# polytag.net
KiCad netlist of a schematic drawn in EAGLE
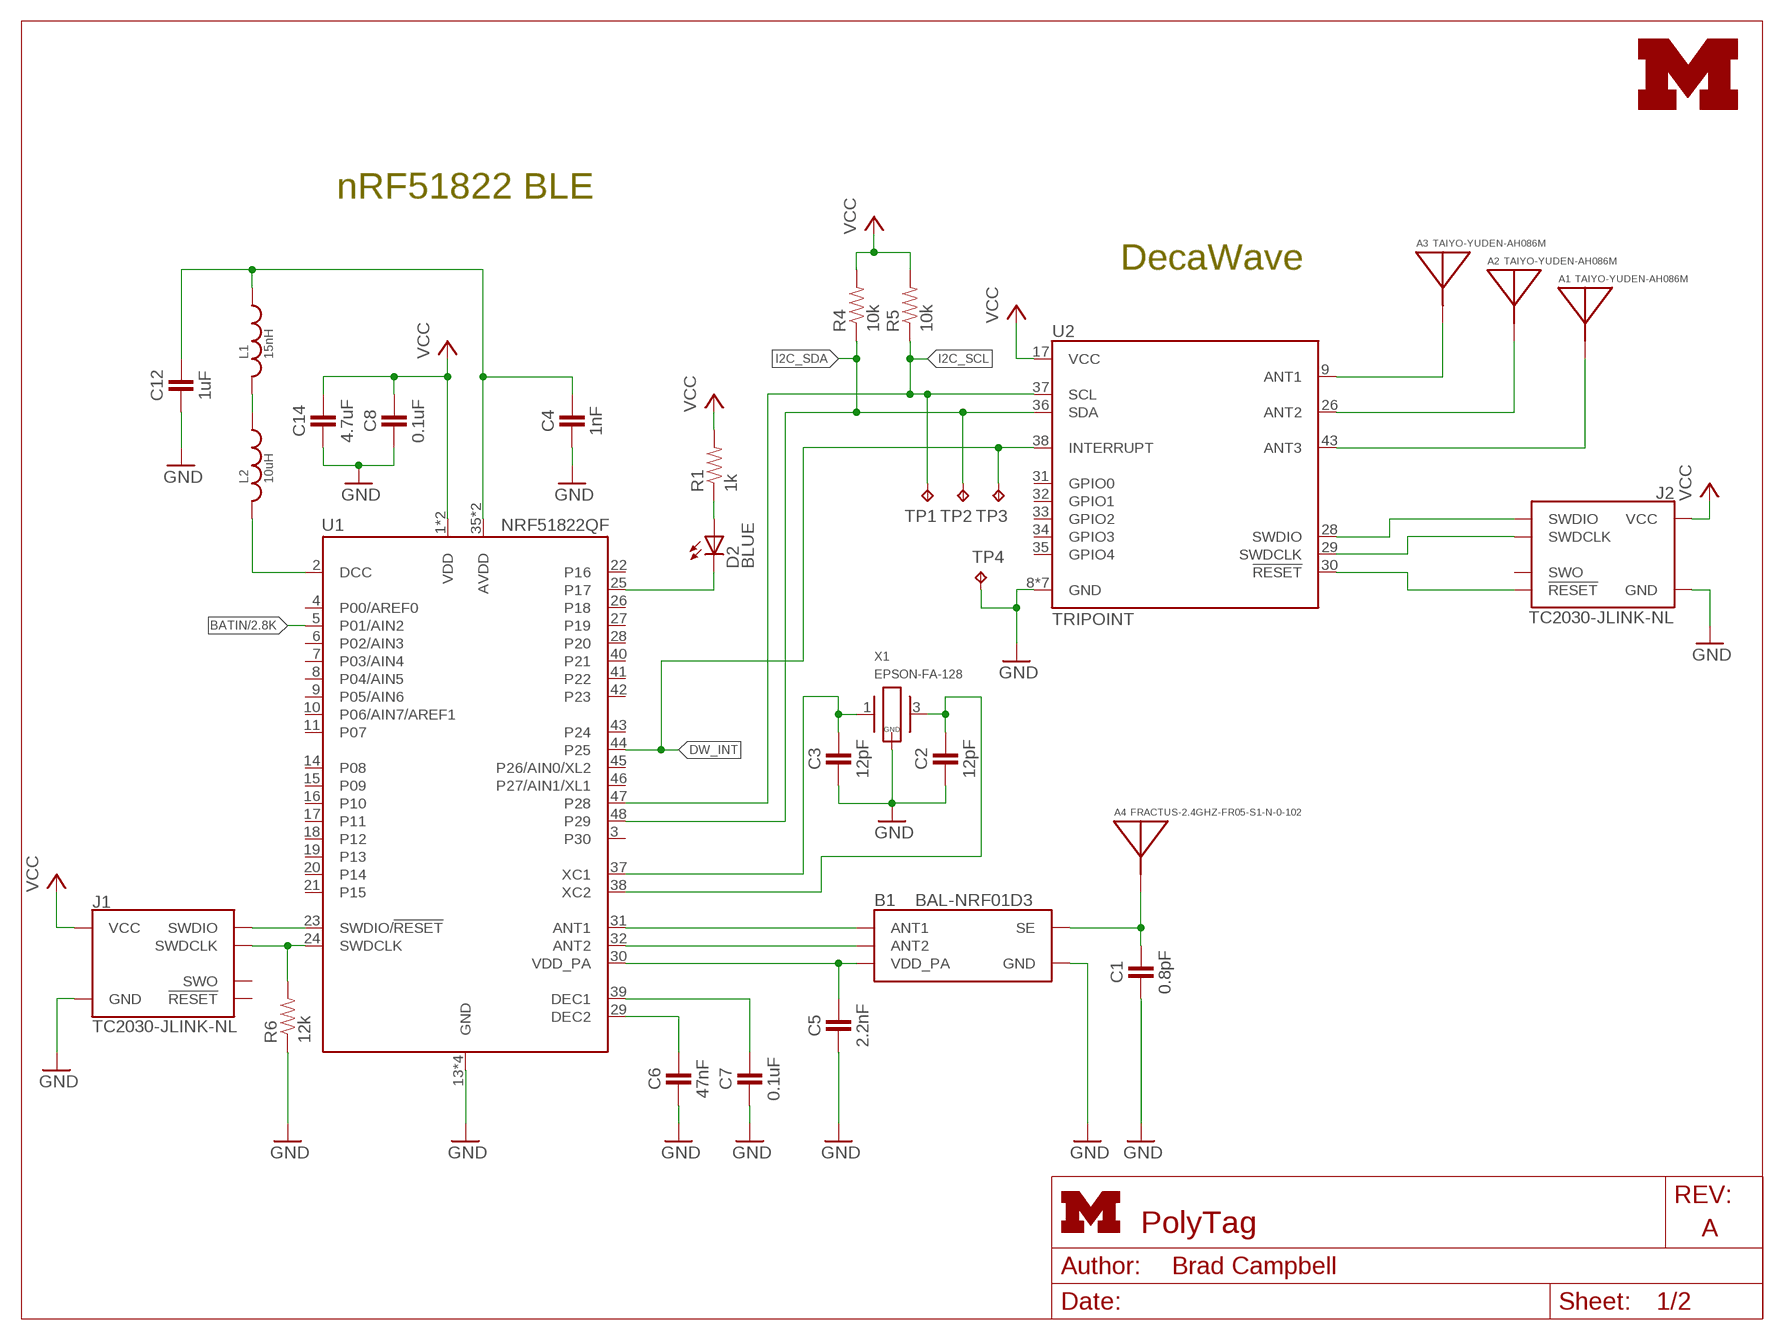
[diagram p0: schematic, sheet 1]
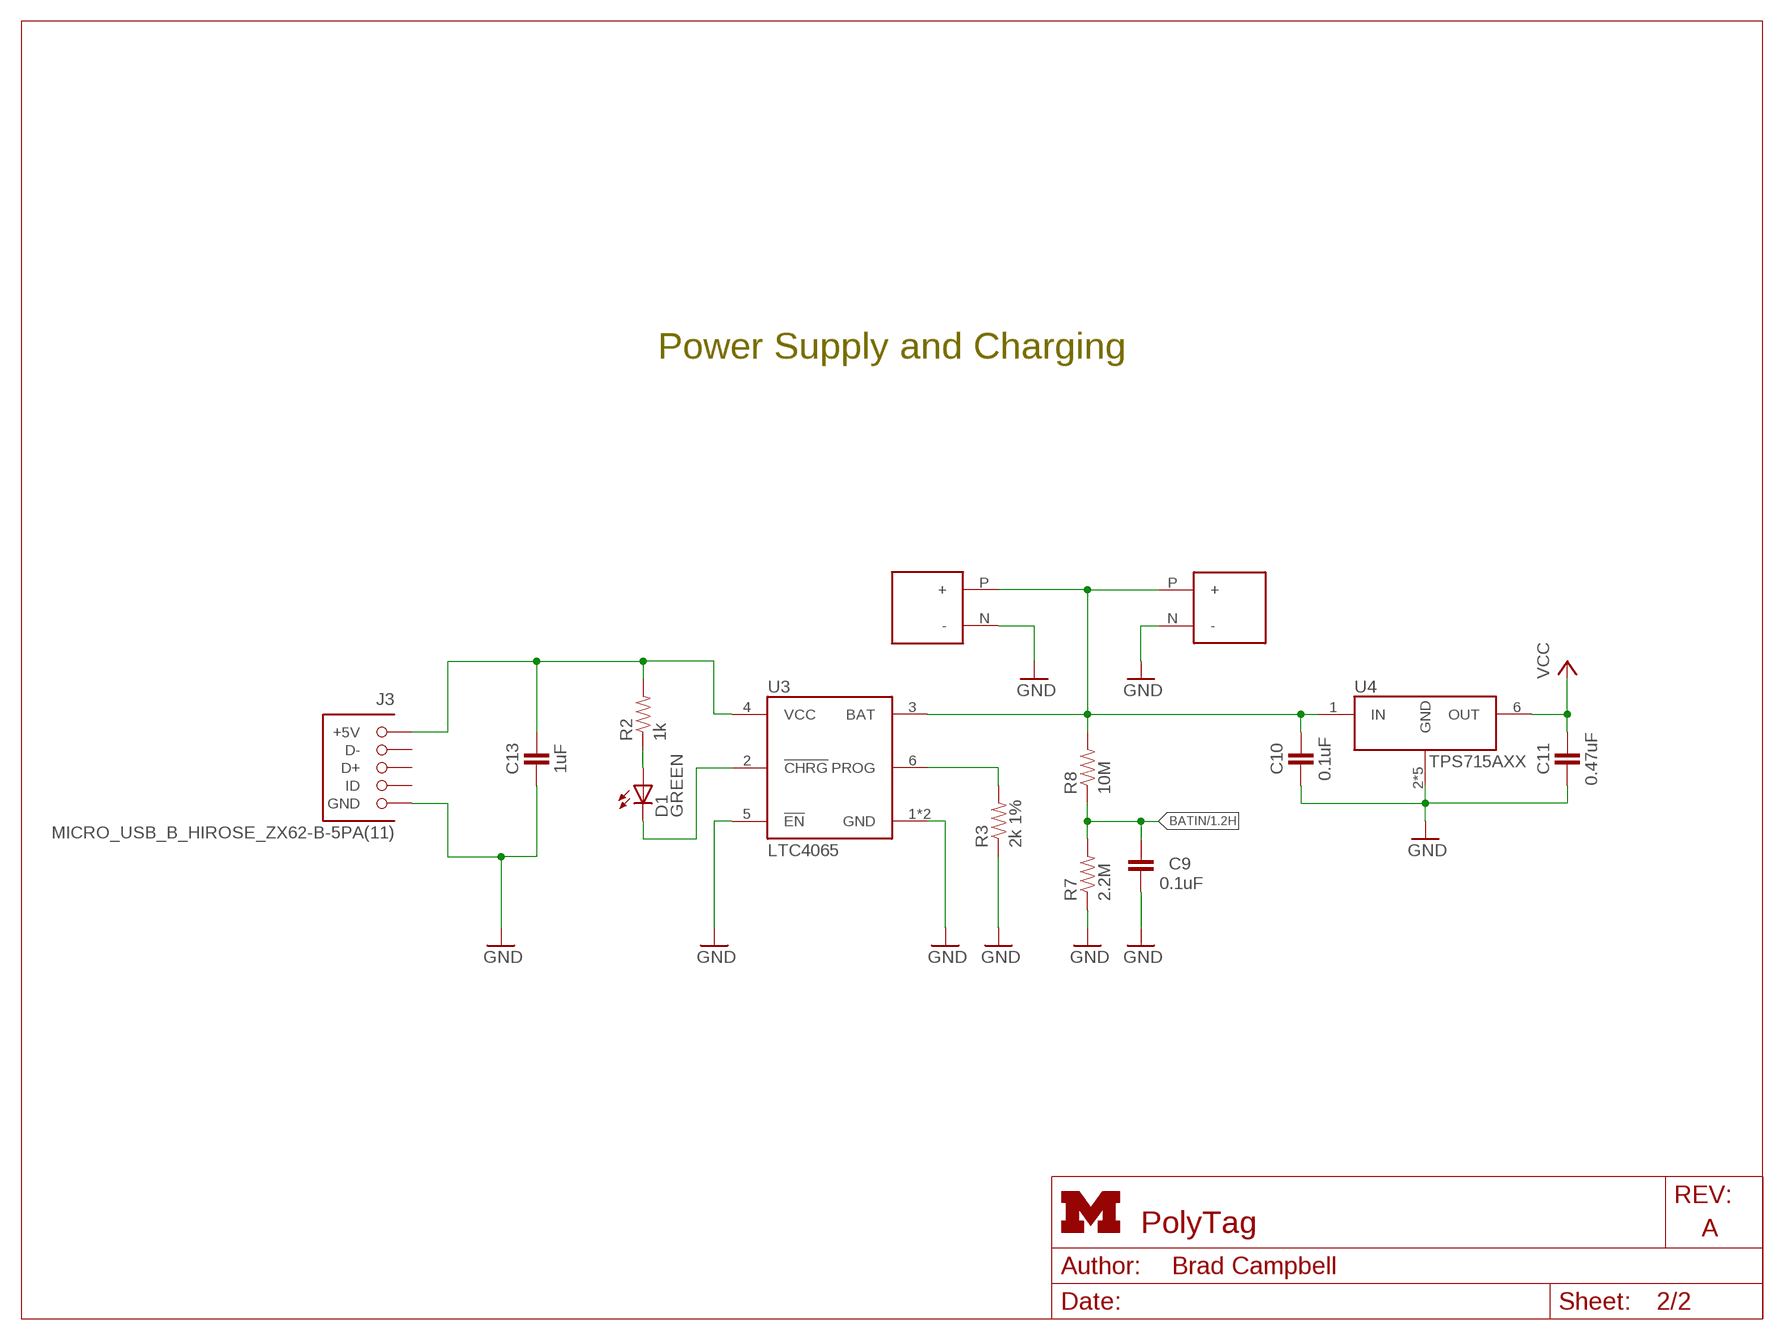
[diagram p1: schematic, sheet 2]

(export (version "E")
  (design (tool "Eeschema 10.0.6"))
  (components
    (comp (ref "A1")
      (value "TAIYO-YUDEN-AH086M")
      (footprint "eagle-import:TAIYO-YUDEN-AH086M")
      (libsource (lib "eagle-import") (part "TAIYO-YUDEN-AH086M"))
    )
    (comp (ref "A2")
      (value "TAIYO-YUDEN-AH086M")
      (footprint "eagle-import:TAIYO-YUDEN-AH086M")
      (libsource (lib "eagle-import") (part "TAIYO-YUDEN-AH086M"))
    )
    (comp (ref "A3")
      (value "TAIYO-YUDEN-AH086M")
      (footprint "eagle-import:TAIYO-YUDEN-AH086M")
      (libsource (lib "eagle-import") (part "TAIYO-YUDEN-AH086M"))
    )
    (comp (ref "A4")
      (value "FRACTUS-2.4GHZ-FR05-S1-N-0-102")
      (footprint "eagle-import:FRACTUS-ANTENNA-FR05-S1-N-0-102")
      (libsource (lib "eagle-import") (part "FRACTUS-2.4GHZ-FR05-S1-N-0-102"))
    )
    (comp (ref "B1")
      (value "BAL-NRF01D3")
      (footprint "eagle-import:BAL-NRF01D3")
      (libsource (lib "eagle-import") (part "BAL-NRF01D3"))
    )
    (comp (ref "C1")
      (value "0.8pF")
      (footprint "eagle-import:0402_CAP")
      (libsource (lib "eagle-import") (part "CAPACITOR"))
    )
    (comp (ref "C2")
      (value "12pF")
      (footprint "eagle-import:0402_CAP")
      (libsource (lib "eagle-import") (part "CAPACITOR"))
    )
    (comp (ref "C3")
      (value "12pF")
      (footprint "eagle-import:0402_CAP")
      (libsource (lib "eagle-import") (part "CAPACITOR"))
    )
    (comp (ref "C4")
      (value "1nF")
      (footprint "eagle-import:0402_CAP")
      (libsource (lib "eagle-import") (part "CAPACITOR"))
    )
    (comp (ref "C5")
      (value "2.2nF")
      (footprint "eagle-import:0402_CAP")
      (libsource (lib "eagle-import") (part "CAPACITOR"))
    )
    (comp (ref "C6")
      (value "47nF")
      (footprint "eagle-import:0402_CAP")
      (libsource (lib "eagle-import") (part "CAPACITOR"))
    )
    (comp (ref "C7")
      (value "0.1uF")
      (footprint "eagle-import:0402_CAP")
      (libsource (lib "eagle-import") (part "CAPACITOR"))
    )
    (comp (ref "C8")
      (value "0.1uF")
      (footprint "eagle-import:0402_CAP")
      (libsource (lib "eagle-import") (part "CAPACITOR"))
    )
    (comp (ref "C12")
      (value "1uF")
      (footprint "eagle-import:0402_CAP")
      (libsource (lib "eagle-import") (part "CAPACITOR"))
    )
    (comp (ref "C14")
      (value "4.7uF")
      (footprint "eagle-import:0402_CAP")
      (libsource (lib "eagle-import") (part "CAPACITOR"))
    )
    (comp (ref "D2")
      (value "BLUE")
      (footprint "eagle-import:LED-0603")
      (libsource (lib "eagle-import") (part "LED0603"))
    )
    (comp (ref "J1")
      (value "TC2030-JLINK-NL")
      (footprint "eagle-import:TC2030-IDC-NL")
      (libsource (lib "eagle-import") (part "TC2030-JLINK-NL"))
    )
    (comp (ref "J2")
      (value "TC2030-JLINK-NL")
      (footprint "eagle-import:TC2030-IDC-NL")
      (libsource (lib "eagle-import") (part "TC2030-JLINK-NL"))
    )
    (comp (ref "L1")
      (value "15nH")
      (footprint "eagle-import:0402_CAP")
      (libsource (lib "eagle-import") (part "INDUCTOR0402"))
    )
    (comp (ref "L2")
      (value "10uH")
      (footprint "eagle-import:0603_CAP")
      (libsource (lib "eagle-import") (part "INDUCTOR0603"))
    )
    (comp (ref "LOGO1")
      (value "UMICH_SOLID_SMALL")
      (footprint "eagle-import:UMICH_SOLID_75MIL")
      (libsource (lib "eagle-import") (part "UMICH_SOLID_SMALL"))
    )
    (comp (ref "R1")
      (value "1k")
      (footprint "eagle-import:0402_RES")
      (libsource (lib "eagle-import") (part "RESISTOR0402_RES"))
    )
    (comp (ref "R4")
      (value "10k")
      (footprint "eagle-import:0402_RES")
      (libsource (lib "eagle-import") (part "RESISTOR0402_RES"))
    )
    (comp (ref "R5")
      (value "10k")
      (footprint "eagle-import:0402_RES")
      (libsource (lib "eagle-import") (part "RESISTOR0402_RES"))
    )
    (comp (ref "R6")
      (value "12k")
      (footprint "eagle-import:0402_RES")
      (libsource (lib "eagle-import") (part "RESISTOR0402_RES"))
    )
    (comp (ref "TP1")
      (value "TPTP06SQ")
      (footprint "eagle-import:TP06SQ")
      (libsource (lib "eagle-import") (part "TPTP06SQ"))
    )
    (comp (ref "TP2")
      (value "TPTP06SQ")
      (footprint "eagle-import:TP06SQ")
      (libsource (lib "eagle-import") (part "TPTP06SQ"))
    )
    (comp (ref "TP3")
      (value "TPTP06SQ")
      (footprint "eagle-import:TP06SQ")
      (libsource (lib "eagle-import") (part "TPTP06SQ"))
    )
    (comp (ref "TP4")
      (value "TPTP06SQ")
      (footprint "eagle-import:TP06SQ")
      (libsource (lib "eagle-import") (part "TPTP06SQ"))
    )
    (comp (ref "U1")
      (value "NRF51822QF")
      (footprint "eagle-import:QFN-48-6MM")
      (libsource (lib "eagle-import") (part "NRF51822QF"))
    )
    (comp (ref "U2")
      (value "TRIPOINT")
      (footprint "eagle-import:TRIPOINT")
      (libsource (lib "eagle-import") (part "TRIPOINT"))
    )
    (comp (ref "X1")
      (value "EPSON-FA-128")
      (footprint "eagle-import:FA-128")
      (libsource (lib "eagle-import") (part "EPSON-FA-128"))
    )
    (comp (ref "C9")
      (value "0.1uF")
      (footprint "eagle-import:0402_CAP")
      (libsource (lib "eagle-import") (part "CAPACITOR"))
    )
    (comp (ref "C10")
      (value "0.1uF")
      (footprint "eagle-import:0402_CAP")
      (libsource (lib "eagle-import") (part "CAPACITOR"))
    )
    (comp (ref "C11")
      (value "0.47uF")
      (footprint "eagle-import:0402_CAP")
      (libsource (lib "eagle-import") (part "CAPACITOR"))
    )
    (comp (ref "C13")
      (value "1uF")
      (footprint "eagle-import:0402_CAP")
      (libsource (lib "eagle-import") (part "CAPACITOR"))
    )
    (comp (ref "D1")
      (value "GREEN")
      (footprint "eagle-import:LED-0603")
      (libsource (lib "eagle-import") (part "LED0603"))
    )
    (comp (ref "J3")
      (value "MICRO_USB_B_HIROSE_ZX62-B-5PA(11)")
      (footprint "eagle-import:USB_MICRO_B-HIROSE-ZX62-B-5PA(11)")
      (libsource (lib "eagle-import") (part "MICRO_USB_B_HIROSE_ZX62-B-5PA(11)"))
    )
    (comp (ref "J4")
      (value "BAT_HOLE")
      (footprint "eagle-import:BATTERY_HOLE")
      (libsource (lib "eagle-import") (part "BAT_HOLE"))
    )
    (comp (ref "J5")
      (value "BAT_HOLE")
      (footprint "eagle-import:BATTERY_HOLE")
      (libsource (lib "eagle-import") (part "BAT_HOLE"))
    )
    (comp (ref "R2")
      (value "1k")
      (footprint "eagle-import:0402_RES")
      (libsource (lib "eagle-import") (part "RESISTOR0402_RES"))
    )
    (comp (ref "R3")
      (value "2k 1%")
      (footprint "eagle-import:0402_RES")
      (libsource (lib "eagle-import") (part "RESISTOR0402_RES"))
    )
    (comp (ref "R7")
      (value "2.2M")
      (footprint "eagle-import:0402_RES")
      (libsource (lib "eagle-import") (part "RESISTOR0402_RES"))
    )
    (comp (ref "R8")
      (value "10M")
      (footprint "eagle-import:0402_RES")
      (libsource (lib "eagle-import") (part "RESISTOR0402_RES"))
    )
    (comp (ref "U3")
      (value "LTC4065")
      (footprint "eagle-import:DFN-6_2MM")
      (libsource (lib "eagle-import") (part "LTC4065"))
    )
    (comp (ref "U4")
      (value "TPS715AXX")
      (footprint "eagle-import:WDFN-6")
      (libsource (lib "eagle-import") (part "TPS715AXX"))
    )
  )
  (nets
    (net (code "1") (name "BATIN") (class "Default")
      (node (ref "C9") (pin "2") (pinfunction "2_2") (pintype "bidirectional"))
      (node (ref "R7") (pin "2") (pinfunction "2_2") (pintype "passive"))
      (node (ref "R8") (pin "1") (pinfunction "1_1") (pintype "passive"))
      (node (ref "U1") (pin "5") (pinfunction "P01/AIN2_5") (pintype "bidirectional"))
    )
    (net (code "2") (name "DW_INT") (class "Default")
      (node (ref "TP3") (pin "TP") (pinfunction "TP_TP") (pintype "input"))
      (node (ref "U1") (pin "44") (pinfunction "P25_44") (pintype "bidirectional"))
      (node (ref "U2") (pin "38") (pinfunction "INTERRUPT_38") (pintype "bidirectional"))
    )
    (net (code "3") (name "GND") (class "Default")
      (node (ref "B1") (pin "GND") (pinfunction "GND_GND") (pintype "bidirectional"))
      (node (ref "C1") (pin "2") (pinfunction "2_2") (pintype "bidirectional"))
      (node (ref "C10") (pin "2") (pinfunction "2_2") (pintype "bidirectional"))
      (node (ref "C11") (pin "2") (pinfunction "2_2") (pintype "bidirectional"))
      (node (ref "C12") (pin "2") (pinfunction "2_2") (pintype "bidirectional"))
      (node (ref "C13") (pin "2") (pinfunction "2_2") (pintype "bidirectional"))
      (node (ref "C14") (pin "2") (pinfunction "2_2") (pintype "bidirectional"))
      (node (ref "C2") (pin "2") (pinfunction "2_2") (pintype "bidirectional"))
      (node (ref "C3") (pin "2") (pinfunction "2_2") (pintype "bidirectional"))
      (node (ref "C4") (pin "2") (pinfunction "2_2") (pintype "bidirectional"))
      (node (ref "C5") (pin "2") (pinfunction "2_2") (pintype "bidirectional"))
      (node (ref "C6") (pin "2") (pinfunction "2_2") (pintype "bidirectional"))
      (node (ref "C7") (pin "2") (pinfunction "2_2") (pintype "bidirectional"))
      (node (ref "C8") (pin "2") (pinfunction "2_2") (pintype "bidirectional"))
      (node (ref "C9") (pin "1") (pinfunction "1_1") (pintype "bidirectional"))
      (node (ref "J1") (pin "5") (pinfunction "GND_5") (pintype "bidirectional"))
      (node (ref "J2") (pin "5") (pinfunction "GND_5") (pintype "bidirectional"))
      (node (ref "J3") (pin "5") (pinfunction "GND_5") (pintype "bidirectional"))
      (node (ref "J4") (pin "N") (pinfunction "-_N") (pintype "bidirectional"))
      (node (ref "J5") (pin "N") (pinfunction "-_N") (pintype "bidirectional"))
      (node (ref "R3") (pin "1") (pinfunction "1_1") (pintype "passive"))
      (node (ref "R6") (pin "1") (pinfunction "1_1") (pintype "passive"))
      (node (ref "R7") (pin "1") (pinfunction "1_1") (pintype "passive"))
      (node (ref "TP4") (pin "TP") (pinfunction "TP_TP") (pintype "input"))
      (node (ref "U1") (pin "13") (pinfunction "GND_13") (pintype "bidirectional"))
      (node (ref "U1") (pin "33") (pinfunction "GND_33") (pintype "bidirectional"))
      (node (ref "U1") (pin "34") (pinfunction "GND_34") (pintype "bidirectional"))
      (node (ref "U1") (pin "GND") (pinfunction "GND_GND") (pintype "bidirectional"))
      (node (ref "U2") (pin "10") (pinfunction "GND_10") (pintype "bidirectional"))
      (node (ref "U2") (pin "18") (pinfunction "GND_18") (pintype "bidirectional"))
      (node (ref "U2") (pin "25") (pinfunction "GND_25") (pintype "bidirectional"))
      (node (ref "U2") (pin "27") (pinfunction "GND_27") (pintype "bidirectional"))
      (node (ref "U2") (pin "42") (pinfunction "GND_42") (pintype "bidirectional"))
      (node (ref "U2") (pin "44") (pinfunction "GND_44") (pintype "bidirectional"))
      (node (ref "U2") (pin "8") (pinfunction "GND_8") (pintype "bidirectional"))
      (node (ref "U3") (pin "1") (pinfunction "GND_1") (pintype "bidirectional"))
      (node (ref "U3") (pin "5") (pinfunction "~{EN}_5") (pintype "bidirectional"))
      (node (ref "U3") (pin "7") (pinfunction "GND_7") (pintype "bidirectional"))
      (node (ref "U4") (pin "2") (pinfunction "GND_2") (pintype "bidirectional"))
      (node (ref "U4") (pin "3") (pinfunction "GND_3") (pintype "bidirectional"))
      (node (ref "U4") (pin "4") (pinfunction "GND_4") (pintype "bidirectional"))
      (node (ref "U4") (pin "5") (pinfunction "GND_5") (pintype "bidirectional"))
      (node (ref "U4") (pin "TP3") (pinfunction "GND_TP3") (pintype "bidirectional"))
      (node (ref "X1") (pin "2") (pinfunction "GND_2") (pintype "bidirectional"))
      (node (ref "X1") (pin "4") (pinfunction "GND_4") (pintype "bidirectional"))
    )
    (net (code "4") (name "I2C_SCL") (class "Default")
      (node (ref "R5") (pin "1") (pinfunction "1_1") (pintype "passive"))
      (node (ref "TP1") (pin "TP") (pinfunction "TP_TP") (pintype "input"))
      (node (ref "U1") (pin "47") (pinfunction "P28_47") (pintype "bidirectional"))
      (node (ref "U2") (pin "37") (pinfunction "SCL_37") (pintype "bidirectional"))
    )
    (net (code "5") (name "I2C_SDA") (class "Default")
      (node (ref "R4") (pin "1") (pinfunction "1_1") (pintype "passive"))
      (node (ref "TP2") (pin "TP") (pinfunction "TP_TP") (pintype "input"))
      (node (ref "U1") (pin "48") (pinfunction "P29_48") (pintype "bidirectional"))
      (node (ref "U2") (pin "36") (pinfunction "SDA_36") (pintype "bidirectional"))
    )
    (net (code "6") (name "Net-(A1-ANTENNA)") (class "Default")
      (node (ref "A1") (pin "A") (pinfunction "ANTENNA_A") (pintype "bidirectional"))
      (node (ref "U2") (pin "43") (pinfunction "ANT3_43") (pintype "bidirectional"))
    )
    (net (code "7") (name "Net-(A2-ANTENNA)") (class "Default")
      (node (ref "A2") (pin "A") (pinfunction "ANTENNA_A") (pintype "bidirectional"))
      (node (ref "U2") (pin "26") (pinfunction "ANT2_26") (pintype "bidirectional"))
    )
    (net (code "8") (name "Net-(A3-ANTENNA)") (class "Default")
      (node (ref "A3") (pin "A") (pinfunction "ANTENNA_A") (pintype "bidirectional"))
      (node (ref "U2") (pin "9") (pinfunction "ANT1_9") (pintype "bidirectional"))
    )
    (net (code "9") (name "Net-(A4-ANTENNA)") (class "Default")
      (node (ref "A4") (pin "1") (pinfunction "ANTENNA_1") (pintype "bidirectional"))
      (node (ref "B1") (pin "SE") (pinfunction "SE_SE") (pintype "bidirectional"))
      (node (ref "C1") (pin "1") (pinfunction "1_1") (pintype "bidirectional"))
    )
    (net (code "10") (name "Net-(B1-VDD_PA)") (class "Default")
      (node (ref "B1") (pin "VCC") (pinfunction "VDD_PA_VCC") (pintype "bidirectional"))
      (node (ref "C5") (pin "1") (pinfunction "1_1") (pintype "bidirectional"))
      (node (ref "U1") (pin "30") (pinfunction "VDD_PA_30") (pintype "bidirectional"))
    )
    (net (code "11") (name "Net-(C12-Pad1)") (class "Default")
      (node (ref "C12") (pin "1") (pinfunction "1_1") (pintype "bidirectional"))
      (node (ref "C4") (pin "1") (pinfunction "1_1") (pintype "bidirectional"))
      (node (ref "L1") (pin "1") (pinfunction "1_1") (pintype "bidirectional"))
      (node (ref "U1") (pin "35") (pinfunction "AVDD_35") (pintype "bidirectional"))
      (node (ref "U1") (pin "36") (pinfunction "AVDD_36") (pintype "bidirectional"))
    )
    (net (code "12") (name "Net-(D1-PadA)") (class "Default")
      (node (ref "D1") (pin "A") (pinfunction "A_A") (pintype "passive"))
      (node (ref "R2") (pin "1") (pinfunction "1_1") (pintype "passive"))
    )
    (net (code "13") (name "Net-(D2-PadA)") (class "Default")
      (node (ref "D2") (pin "A") (pinfunction "A_A") (pintype "passive"))
      (node (ref "R1") (pin "1") (pinfunction "1_1") (pintype "passive"))
    )
    (net (code "14") (name "Net-(J1-SWDCLK)") (class "Default")
      (node (ref "J1") (pin "4") (pinfunction "SWDCLK_4") (pintype "bidirectional"))
      (node (ref "R6") (pin "2") (pinfunction "2_2") (pintype "passive"))
      (node (ref "U1") (pin "24") (pinfunction "SWDCLK_24") (pintype "bidirectional"))
    )
    (net (code "15") (name "Net-(J1-SWDIO)") (class "Default")
      (node (ref "J1") (pin "2") (pinfunction "SWDIO_2") (pintype "bidirectional"))
      (node (ref "U1") (pin "23") (pinfunction "SWDIO/~{RESET}_23") (pintype "bidirectional"))
    )
    (net (code "16") (name "Net-(J2-SWDCLK)") (class "Default")
      (node (ref "J2") (pin "4") (pinfunction "SWDCLK_4") (pintype "bidirectional"))
      (node (ref "U2") (pin "29") (pinfunction "SWDCLK_29") (pintype "bidirectional"))
    )
    (net (code "17") (name "Net-(J2-SWDIO)") (class "Default")
      (node (ref "J2") (pin "2") (pinfunction "SWDIO_2") (pintype "bidirectional"))
      (node (ref "U2") (pin "28") (pinfunction "SWDIO_28") (pintype "bidirectional"))
    )
    (net (code "18") (name "Net-(J2-~{RESET})") (class "Default")
      (node (ref "J2") (pin "3") (pinfunction "~{RESET}_3") (pintype "bidirectional"))
      (node (ref "U2") (pin "30") (pinfunction "~{RESET}_30") (pintype "bidirectional"))
    )
    (net (code "19") (name "Net-(J3-+5V)") (class "Default")
      (node (ref "C13") (pin "1") (pinfunction "1_1") (pintype "bidirectional"))
      (node (ref "J3") (pin "1") (pinfunction "+5V_1") (pintype "bidirectional"))
      (node (ref "R2") (pin "2") (pinfunction "2_2") (pintype "passive"))
      (node (ref "U3") (pin "4") (pinfunction "VCC_4") (pintype "bidirectional"))
    )
    (net (code "20") (name "Net-(J4-+)") (class "Default")
      (node (ref "C10") (pin "1") (pinfunction "1_1") (pintype "bidirectional"))
      (node (ref "J4") (pin "P") (pinfunction "+_P") (pintype "bidirectional"))
      (node (ref "J5") (pin "P") (pinfunction "+_P") (pintype "bidirectional"))
      (node (ref "R8") (pin "2") (pinfunction "2_2") (pintype "passive"))
      (node (ref "U3") (pin "3") (pinfunction "BAT_3") (pintype "bidirectional"))
      (node (ref "U4") (pin "1") (pinfunction "IN_1") (pintype "bidirectional"))
    )
    (net (code "21") (name "Net-(L1-Pad2)") (class "Default")
      (node (ref "L1") (pin "2") (pinfunction "2_2") (pintype "bidirectional"))
      (node (ref "L2") (pin "1") (pinfunction "1_1") (pintype "bidirectional"))
    )
    (net (code "22") (name "Net-(U1-ANT1)") (class "Default")
      (node (ref "B1") (pin "ANT1") (pinfunction "ANT1_ANT1") (pintype "bidirectional"))
      (node (ref "U1") (pin "31") (pinfunction "ANT1_31") (pintype "bidirectional"))
    )
    (net (code "23") (name "Net-(U1-ANT2)") (class "Default")
      (node (ref "B1") (pin "ANT2") (pinfunction "ANT2_ANT2") (pintype "bidirectional"))
      (node (ref "U1") (pin "32") (pinfunction "ANT2_32") (pintype "bidirectional"))
    )
    (net (code "24") (name "Net-(U1-DCC)") (class "Default")
      (node (ref "L2") (pin "2") (pinfunction "2_2") (pintype "bidirectional"))
      (node (ref "U1") (pin "2") (pinfunction "DCC_2") (pintype "bidirectional"))
    )
    (net (code "25") (name "Net-(U1-DEC1)") (class "Default")
      (node (ref "C7") (pin "1") (pinfunction "1_1") (pintype "bidirectional"))
      (node (ref "U1") (pin "39") (pinfunction "DEC1_39") (pintype "bidirectional"))
    )
    (net (code "26") (name "Net-(U1-DEC2)") (class "Default")
      (node (ref "C6") (pin "1") (pinfunction "1_1") (pintype "bidirectional"))
      (node (ref "U1") (pin "29") (pinfunction "DEC2_29") (pintype "bidirectional"))
    )
    (net (code "27") (name "Net-(U1-P17)") (class "Default")
      (node (ref "D2") (pin "C") (pinfunction "C_C") (pintype "passive"))
      (node (ref "U1") (pin "25") (pinfunction "P17_25") (pintype "bidirectional"))
    )
    (net (code "28") (name "Net-(U1-XC1)") (class "Default")
      (node (ref "C3") (pin "1") (pinfunction "1_1") (pintype "bidirectional"))
      (node (ref "U1") (pin "37") (pinfunction "XC1_37") (pintype "bidirectional"))
      (node (ref "X1") (pin "1") (pinfunction "1_1") (pintype "bidirectional"))
    )
    (net (code "29") (name "Net-(U1-XC2)") (class "Default")
      (node (ref "C2") (pin "1") (pinfunction "1_1") (pintype "bidirectional"))
      (node (ref "U1") (pin "38") (pinfunction "XC2_38") (pintype "bidirectional"))
      (node (ref "X1") (pin "3") (pinfunction "2_3") (pintype "bidirectional"))
    )
    (net (code "30") (name "Net-(U3-PROG)") (class "Default")
      (node (ref "R3") (pin "2") (pinfunction "2_2") (pintype "passive"))
      (node (ref "U3") (pin "6") (pinfunction "PROG_6") (pintype "bidirectional"))
    )
    (net (code "31") (name "Net-(U3-~{CHRG})") (class "Default")
      (node (ref "D1") (pin "C") (pinfunction "C_C") (pintype "passive"))
      (node (ref "U3") (pin "2") (pinfunction "~{CHRG}_2") (pintype "bidirectional"))
    )
    (net (code "32") (name "VCC") (class "Default")
      (node (ref "C11") (pin "1") (pinfunction "1_1") (pintype "bidirectional"))
      (node (ref "C14") (pin "1") (pinfunction "1_1") (pintype "bidirectional"))
      (node (ref "C8") (pin "1") (pinfunction "1_1") (pintype "bidirectional"))
      (node (ref "J1") (pin "1") (pinfunction "VCC_1") (pintype "bidirectional"))
      (node (ref "J2") (pin "1") (pinfunction "VCC_1") (pintype "bidirectional"))
      (node (ref "R1") (pin "2") (pinfunction "2_2") (pintype "passive"))
      (node (ref "R4") (pin "2") (pinfunction "2_2") (pintype "passive"))
      (node (ref "R5") (pin "2") (pinfunction "2_2") (pintype "passive"))
      (node (ref "U1") (pin "1") (pinfunction "VDD_1") (pintype "bidirectional"))
      (node (ref "U1") (pin "12") (pinfunction "VDD_12") (pintype "bidirectional"))
      (node (ref "U2") (pin "17") (pinfunction "VCC_17") (pintype "bidirectional"))
      (node (ref "U4") (pin "6") (pinfunction "OUT_6") (pintype "bidirectional"))
    )
    (net (code "33") (name "unconnected-(J1-SWO-Pad6)") (class "Default")
      (node (ref "J1") (pin "6") (pinfunction "SWO_6") (pintype "bidirectional"))
    )
    (net (code "34") (name "unconnected-(J1-~{RESET}-Pad3)") (class "Default")
      (node (ref "J1") (pin "3") (pinfunction "~{RESET}_3") (pintype "bidirectional"))
    )
    (net (code "35") (name "unconnected-(J2-SWO-Pad6)") (class "Default")
      (node (ref "J2") (pin "6") (pinfunction "SWO_6") (pintype "bidirectional"))
    )
    (net (code "36") (name "unconnected-(J3-D+-Pad3)") (class "Default")
      (node (ref "J3") (pin "3") (pinfunction "D+_3") (pintype "bidirectional"))
    )
    (net (code "37") (name "unconnected-(J3-D--Pad2)") (class "Default")
      (node (ref "J3") (pin "2") (pinfunction "D-_2") (pintype "bidirectional"))
    )
    (net (code "38") (name "unconnected-(J3-ID-Pad4)") (class "Default")
      (node (ref "J3") (pin "4") (pinfunction "ID_4") (pintype "bidirectional"))
    )
    (net (code "39") (name "unconnected-(U1-P00{slash}AREF0-Pad4)") (class "Default")
      (node (ref "U1") (pin "4") (pinfunction "P00/AREF0_4") (pintype "bidirectional"))
    )
    (net (code "40") (name "unconnected-(U1-P02{slash}AIN3-Pad6)") (class "Default")
      (node (ref "U1") (pin "6") (pinfunction "P02/AIN3_6") (pintype "bidirectional"))
    )
    (net (code "41") (name "unconnected-(U1-P03{slash}AIN4-Pad7)") (class "Default")
      (node (ref "U1") (pin "7") (pinfunction "P03/AIN4_7") (pintype "bidirectional"))
    )
    (net (code "42") (name "unconnected-(U1-P04{slash}AIN5-Pad8)") (class "Default")
      (node (ref "U1") (pin "8") (pinfunction "P04/AIN5_8") (pintype "bidirectional"))
    )
    (net (code "43") (name "unconnected-(U1-P05{slash}AIN6-Pad9)") (class "Default")
      (node (ref "U1") (pin "9") (pinfunction "P05/AIN6_9") (pintype "bidirectional"))
    )
    (net (code "44") (name "unconnected-(U1-P06{slash}AIN7{slash}AREF1-Pad10)") (class "Default")
      (node (ref "U1") (pin "10") (pinfunction "P06/AIN7/AREF1_10") (pintype "bidirectional"))
    )
    (net (code "45") (name "unconnected-(U1-P07-Pad11)") (class "Default")
      (node (ref "U1") (pin "11") (pinfunction "P07_11") (pintype "bidirectional"))
    )
    (net (code "46") (name "unconnected-(U1-P08-Pad14)") (class "Default")
      (node (ref "U1") (pin "14") (pinfunction "P08_14") (pintype "bidirectional"))
    )
    (net (code "47") (name "unconnected-(U1-P09-Pad15)") (class "Default")
      (node (ref "U1") (pin "15") (pinfunction "P09_15") (pintype "bidirectional"))
    )
    (net (code "48") (name "unconnected-(U1-P10-Pad16)") (class "Default")
      (node (ref "U1") (pin "16") (pinfunction "P10_16") (pintype "bidirectional"))
    )
    (net (code "49") (name "unconnected-(U1-P11-Pad17)") (class "Default")
      (node (ref "U1") (pin "17") (pinfunction "P11_17") (pintype "bidirectional"))
    )
    (net (code "50") (name "unconnected-(U1-P12-Pad18)") (class "Default")
      (node (ref "U1") (pin "18") (pinfunction "P12_18") (pintype "bidirectional"))
    )
    (net (code "51") (name "unconnected-(U1-P13-Pad19)") (class "Default")
      (node (ref "U1") (pin "19") (pinfunction "P13_19") (pintype "bidirectional"))
    )
    (net (code "52") (name "unconnected-(U1-P14-Pad20)") (class "Default")
      (node (ref "U1") (pin "20") (pinfunction "P14_20") (pintype "bidirectional"))
    )
    (net (code "53") (name "unconnected-(U1-P15-Pad21)") (class "Default")
      (node (ref "U1") (pin "21") (pinfunction "P15_21") (pintype "bidirectional"))
    )
    (net (code "54") (name "unconnected-(U1-P16-Pad22)") (class "Default")
      (node (ref "U1") (pin "22") (pinfunction "P16_22") (pintype "bidirectional"))
    )
    (net (code "55") (name "unconnected-(U1-P18-Pad26)") (class "Default")
      (node (ref "U1") (pin "26") (pinfunction "P18_26") (pintype "bidirectional"))
    )
    (net (code "56") (name "unconnected-(U1-P19-Pad27)") (class "Default")
      (node (ref "U1") (pin "27") (pinfunction "P19_27") (pintype "bidirectional"))
    )
    (net (code "57") (name "unconnected-(U1-P20-Pad28)") (class "Default")
      (node (ref "U1") (pin "28") (pinfunction "P20_28") (pintype "bidirectional"))
    )
    (net (code "58") (name "unconnected-(U1-P21-Pad40)") (class "Default")
      (node (ref "U1") (pin "40") (pinfunction "P21_40") (pintype "bidirectional"))
    )
    (net (code "59") (name "unconnected-(U1-P22-Pad41)") (class "Default")
      (node (ref "U1") (pin "41") (pinfunction "P22_41") (pintype "bidirectional"))
    )
    (net (code "60") (name "unconnected-(U1-P23-Pad42)") (class "Default")
      (node (ref "U1") (pin "42") (pinfunction "P23_42") (pintype "bidirectional"))
    )
    (net (code "61") (name "unconnected-(U1-P24-Pad43)") (class "Default")
      (node (ref "U1") (pin "43") (pinfunction "P24_43") (pintype "bidirectional"))
    )
    (net (code "62") (name "unconnected-(U1-P26{slash}AIN0{slash}XL2-Pad45)") (class "Default")
      (node (ref "U1") (pin "45") (pinfunction "P26/AIN0/XL2_45") (pintype "bidirectional"))
    )
    (net (code "63") (name "unconnected-(U1-P27{slash}AIN1{slash}XL1-Pad46)") (class "Default")
      (node (ref "U1") (pin "46") (pinfunction "P27/AIN1/XL1_46") (pintype "bidirectional"))
    )
    (net (code "64") (name "unconnected-(U1-P30-Pad3)") (class "Default")
      (node (ref "U1") (pin "3") (pinfunction "P30_3") (pintype "bidirectional"))
    )
    (net (code "65") (name "unconnected-(U2-GPIO0-Pad31)") (class "Default")
      (node (ref "U2") (pin "31") (pinfunction "GPIO0_31") (pintype "bidirectional"))
    )
    (net (code "66") (name "unconnected-(U2-GPIO1-Pad32)") (class "Default")
      (node (ref "U2") (pin "32") (pinfunction "GPIO1_32") (pintype "bidirectional"))
    )
    (net (code "67") (name "unconnected-(U2-GPIO2-Pad33)") (class "Default")
      (node (ref "U2") (pin "33") (pinfunction "GPIO2_33") (pintype "bidirectional"))
    )
    (net (code "68") (name "unconnected-(U2-GPIO3-Pad34)") (class "Default")
      (node (ref "U2") (pin "34") (pinfunction "GPIO3_34") (pintype "bidirectional"))
    )
    (net (code "69") (name "unconnected-(U2-GPIO4-Pad35)") (class "Default")
      (node (ref "U2") (pin "35") (pinfunction "GPIO4_35") (pintype "bidirectional"))
    )
  )
)
